# Sheet1.net
KiCad netlist of a schematic drawn in Altium Designer
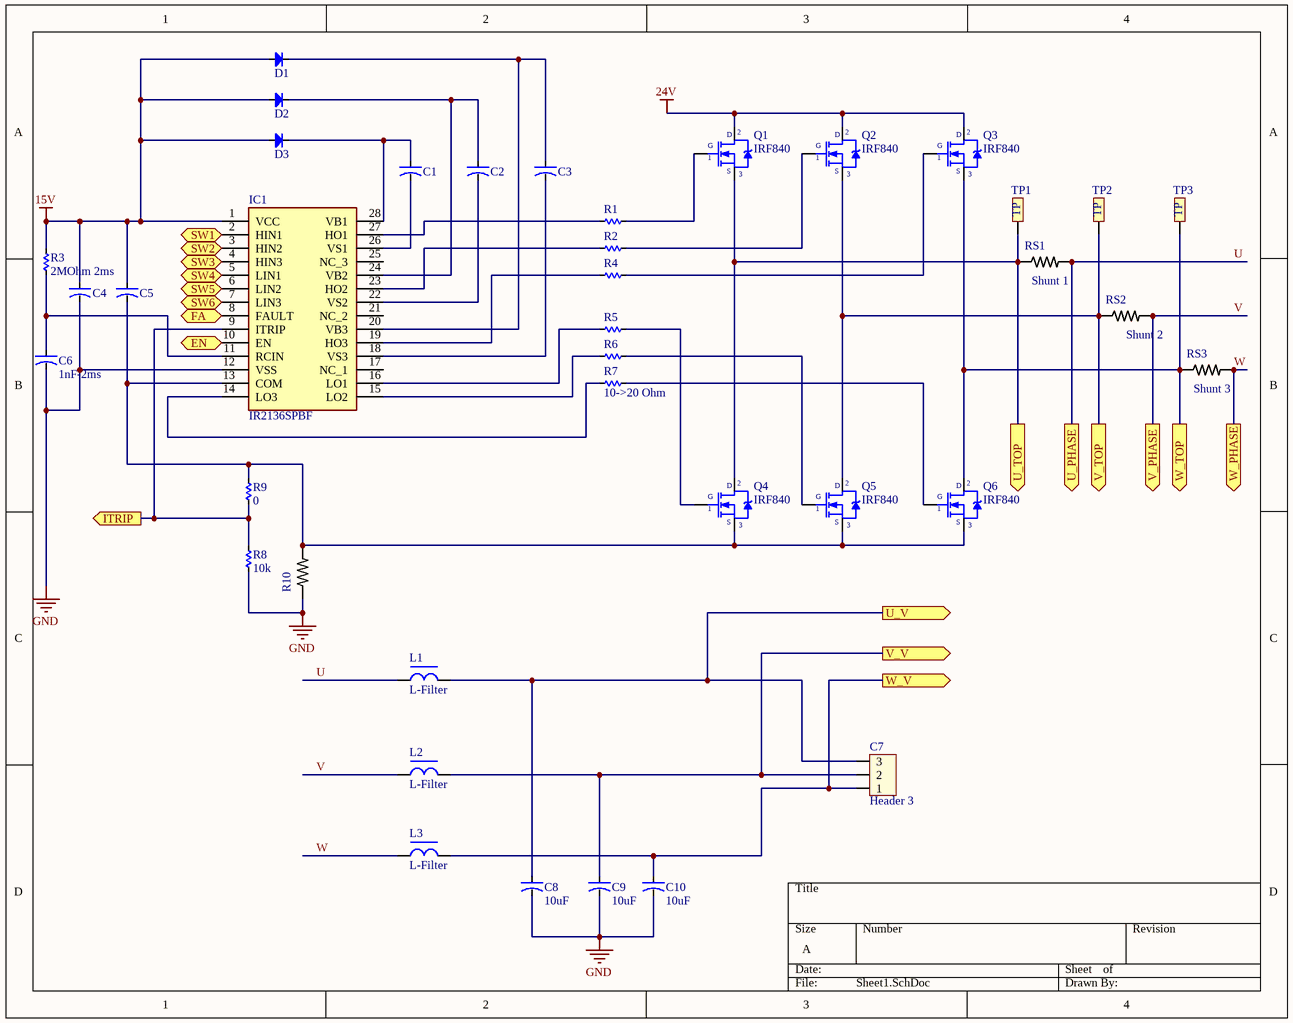
[diagram p0: Sheet1.SchDoc]

(export (version "E")
  (design (tool "Eeschema 10.0.6"))
  (components
    (comp (ref "C1")
      (value "50-100uF")
      (footprint "CA-ALU-5R")
      (description "Capacitor (Semiconductor SIM Model)")
      (fields (field (name "PUBLISHER") "Altium Limited"))
      (libsource (lib "LIBRARY") (part "CN-ALU-DIP"))
    )
    (comp (ref "C2")
      (value "50-100uF")
      (footprint "CA-ALU-5R")
      (description "Capacitor (Semiconductor SIM Model)")
      (fields (field (name "PUBLISHER") "Altium Limited"))
      (libsource (lib "LIBRARY") (part "CN-ALU-DIP"))
    )
    (comp (ref "C3")
      (value "50-100uF")
      (footprint "CA-ALU-5R")
      (description "Capacitor (Semiconductor SIM Model)")
      (fields (field (name "PUBLISHER") "Altium Limited"))
      (libsource (lib "LIBRARY") (part "CN-ALU-DIP"))
    )
    (comp (ref "C4")
      (value "to")
      (footprint "CA-ALU-5R")
      (description "Capacitor (Semiconductor SIM Model)")
      (fields (field (name "PUBLISHER") "Altium Limited"))
      (libsource (lib "LIBRARY") (part "CN-ALU-DIP"))
    )
    (comp (ref "C5")
      (value "to")
      (footprint "CA-ALU-5R")
      (description "Capacitor (Semiconductor SIM Model)")
      (fields (field (name "PUBLISHER") "Altium Limited"))
      (libsource (lib "LIBRARY") (part "CN-ALU-DIP"))
    )
    (comp (ref "C6")
      (value "1nF-2ms")
      (footprint "CA-ALU-2.54")
      (description "Capacitor (Semiconductor SIM Model)")
      (fields (field (name "PUBLISHER") "Altium Limited"))
      (libsource (lib "LIBRARY") (part "CN-ALU-DIP"))
    )
    (comp (ref "C7")
      (value "Header 3")
      (footprint "HED3")
      (description "Header 3 (Green)")
      (libsource (lib "syhaunguyen") (part "Hed3"))
    )
    (comp (ref "C8")
      (value "10uF")
      (footprint "CA-ALU-5R")
      (description "Capacitor (Semiconductor SIM Model)")
      (fields (field (name "PUBLISHER") "Altium Limited"))
      (libsource (lib "LIBRARY") (part "CN-ALU-DIP"))
    )
    (comp (ref "C9")
      (value "10uF")
      (footprint "CA-ALU-5R")
      (description "Capacitor (Semiconductor SIM Model)")
      (fields (field (name "PUBLISHER") "Altium Limited"))
      (libsource (lib "LIBRARY") (part "CN-ALU-DIP"))
    )
    (comp (ref "C10")
      (value "10uF")
      (footprint "CA-ALU-5R")
      (description "Capacitor (Semiconductor SIM Model)")
      (fields (field (name "PUBLISHER") "Altium Limited"))
      (libsource (lib "LIBRARY") (part "CN-ALU-DIP"))
    )
    (comp (ref "D1")
      (value "Diode")
      (footprint "DIO-1A")
      (description "Default Diode")
      (fields (field (name "PUBLISHER") "Altium Limited"))
      (libsource (lib "LIBRARY") (part "Diode"))
    )
    (comp (ref "D2")
      (value "Diode")
      (footprint "DIO-1A")
      (description "Default Diode")
      (fields (field (name "PUBLISHER") "Altium Limited"))
      (libsource (lib "LIBRARY") (part "Diode"))
    )
    (comp (ref "D3")
      (value "Diode")
      (footprint "DIO-1A")
      (description "Default Diode")
      (fields (field (name "PUBLISHER") "Altium Limited"))
      (libsource (lib "LIBRARY") (part "Diode"))
    )
    (comp (ref "IC1")
      (value "IR2136SPBF")
      (footprint "SOIC127P1032X265-28N")
      (description "Integrated Circuit")
      (fields (field (name "MOUSER PART NUMBER") "942-IR2136SPBF") (field (name "RS PART NUMBER") "5412284P"))
      (libsource (lib "SemacSYS") (part "IR2136SPBF"))
    )
    (comp (ref "L1")
      (value "L-Filter")
      (footprint "L-DIP-M-5.3")
      (description "Inductor")
      (libsource (lib "LIBRARY") (part "L-DIP-1"))
    )
    (comp (ref "L2")
      (value "L-Filter")
      (footprint "L-DIP-M-5.3")
      (description "Inductor")
      (libsource (lib "LIBRARY") (part "L-DIP-1"))
    )
    (comp (ref "L3")
      (value "L-Filter")
      (footprint "L-DIP-M-5.3")
      (description "Inductor")
      (libsource (lib "LIBRARY") (part "L-DIP-1"))
    )
    (comp (ref "Q1")
      (value "IRF840")
      (footprint "TO220-123")
      (description "MOSFET N - CHANNEL 500V - 0.75 - 8A - TO-220")
      (libsource (lib "LIBRARY") (part "IRF840"))
    )
    (comp (ref "Q2")
      (value "IRF840")
      (footprint "TO220-123")
      (description "MOSFET N - CHANNEL 500V - 0.75 - 8A - TO-220")
      (libsource (lib "LIBRARY") (part "IRF840"))
    )
    (comp (ref "Q3")
      (value "IRF840")
      (footprint "TO220-123")
      (description "MOSFET N - CHANNEL 500V - 0.75 - 8A - TO-220")
      (libsource (lib "LIBRARY") (part "IRF840"))
    )
    (comp (ref "Q4")
      (value "IRF840")
      (footprint "TO220-123")
      (description "MOSFET N - CHANNEL 500V - 0.75 - 8A - TO-220")
      (libsource (lib "LIBRARY") (part "IRF840"))
    )
    (comp (ref "Q5")
      (value "IRF840")
      (footprint "TO220-123")
      (description "MOSFET N - CHANNEL 500V - 0.75 - 8A - TO-220")
      (libsource (lib "LIBRARY") (part "IRF840"))
    )
    (comp (ref "Q6")
      (value "IRF840")
      (footprint "TO220-123")
      (description "MOSFET N - CHANNEL 500V - 0.75 - 8A - TO-220")
      (libsource (lib "LIBRARY") (part "IRF840"))
    )
    (comp (ref "R1")
      (value "10->20 Ohm")
      (footprint "RES-1/2W")
      (description "Res")
      (fields
        (field (name "MANUFACTURER") "Generic Components")
        (field (name "PUBLISHER") "Altium Hobart Technology Centre")
      )
      (libsource (lib "LIBRARY1") (part "Res"))
    )
    (comp (ref "R2")
      (value "1K10->20 Ohm")
      (footprint "RES-1/2W")
      (description "Res")
      (fields
        (field (name "MANUFACTURER") "Generic Components")
        (field (name "PUBLISHER") "Altium Hobart Technology Centre")
      )
      (libsource (lib "LIBRARY1") (part "Res"))
    )
    (comp (ref "R3")
      (value "2MOhm 2ms")
      (footprint "RES-1/2W")
      (description "Res")
      (fields
        (field (name "MANUFACTURER") "Generic Components")
        (field (name "PUBLISHER") "Altium Hobart Technology Centre")
      )
      (libsource (lib "LIBRARY1") (part "Res"))
    )
    (comp (ref "R4")
      (value "10->20 Ohm")
      (footprint "RES-1/2W")
      (description "Res")
      (fields
        (field (name "MANUFACTURER") "Generic Components")
        (field (name "PUBLISHER") "Altium Hobart Technology Centre")
      )
      (libsource (lib "LIBRARY1") (part "Res"))
    )
    (comp (ref "R5")
      (value "10->20 Ohm")
      (footprint "RES-1/2W")
      (description "Res")
      (fields
        (field (name "MANUFACTURER") "Generic Components")
        (field (name "PUBLISHER") "Altium Hobart Technology Centre")
      )
      (libsource (lib "LIBRARY1") (part "Res"))
    )
    (comp (ref "R6")
      (value "10->20 Ohm")
      (footprint "RES-1/2W")
      (description "Res")
      (fields
        (field (name "MANUFACTURER") "Generic Components")
        (field (name "PUBLISHER") "Altium Hobart Technology Centre")
      )
      (libsource (lib "LIBRARY1") (part "Res"))
    )
    (comp (ref "R7")
      (value "10->20 Ohm")
      (footprint "RES-1/2W")
      (description "Res")
      (fields
        (field (name "MANUFACTURER") "Generic Components")
        (field (name "PUBLISHER") "Altium Hobart Technology Centre")
      )
      (libsource (lib "LIBRARY1") (part "Res"))
    )
    (comp (ref "R8")
      (value "10k")
      (footprint "RES-1/2W")
      (description "Res")
      (fields
        (field (name "MANUFACTURER") "Generic Components")
        (field (name "PUBLISHER") "Altium Hobart Technology Centre")
      )
      (libsource (lib "LIBRARY1") (part "Res"))
    )
    (comp (ref "R9")
      (value "0")
      (footprint "RES-1/2W")
      (description "Res")
      (fields
        (field (name "MANUFACTURER") "Generic Components")
        (field (name "PUBLISHER") "Altium Hobart Technology Centre")
      )
      (libsource (lib "LIBRARY1") (part "Res"))
    )
    (comp (ref "R10")
      (value "1-1625873-0")
      (footprint "*RESAD640W45L370D200")
      (description "RS LR0204 RESISTOR KIT")
      (fields (field (name "MF") "TE Connectivity AMP Connectors") (field (name "MP") "RES KIT LR0204R"))
      (libsource (lib "RES_KIT_LR0204R") (part "RES_KIT_LR0204R"))
    )
    (comp (ref "RS1")
      (value "1-1625873-0")
      (footprint "*RESAD640W45L370D200")
      (description "RS LR0204 RESISTOR KIT")
      (fields (field (name "MF") "TE Connectivity AMP Connectors") (field (name "MP") "RES KIT LR0204R"))
      (libsource (lib "SemacSYS") (part "RES_KIT_LR0204R"))
    )
    (comp (ref "RS2")
      (value "1-1625873-0")
      (footprint "*RESAD640W45L370D200")
      (description "RS LR0204 RESISTOR KIT")
      (fields (field (name "MF") "TE Connectivity AMP Connectors") (field (name "MP") "RES KIT LR0204R"))
      (libsource (lib "SemacSYS") (part "RES_KIT_LR0204R"))
    )
    (comp (ref "RS3")
      (value "1-1625873-0")
      (footprint "*RESAD640W45L370D200")
      (description "RS LR0204 RESISTOR KIT")
      (fields (field (name "MF") "TE Connectivity AMP Connectors") (field (name "MP") "RES KIT LR0204R"))
      (libsource (lib "SemacSYS") (part "RES_KIT_LR0204R"))
    )
    (comp (ref "TP1")
      (value "~")
      (footprint "TP")
      (description "CONNECT 1")
      (libsource (lib "syhaunguyen") (part "TP"))
    )
    (comp (ref "TP2")
      (value "~")
      (footprint "TP")
      (description "CONNECT 1")
      (libsource (lib "syhaunguyen") (part "TP"))
    )
    (comp (ref "TP3")
      (value "~")
      (footprint "TP")
      (description "CONNECT 1")
      (libsource (lib "syhaunguyen") (part "TP"))
    )
  )
  (nets
    (net (code "1") (name "/EN") (class "Default")
      (node (ref "IC1") (pin "10") (pinfunction "EN_10") (pintype "passive"))
    )
    (net (code "2") (name "/FA") (class "Default")
      (node (ref "IC1") (pin "8") (pinfunction "FAULT_8") (pintype "passive"))
    )
    (net (code "3") (name "/ITRIP") (class "Default")
      (node (ref "IC1") (pin "9") (pinfunction "ITRIP_9") (pintype "passive"))
      (node (ref "R8") (pin "1") (pinfunction "1_1") (pintype "passive"))
      (node (ref "R9") (pin "2") (pinfunction "2_2") (pintype "passive"))
    )
    (net (code "4") (name "/SW1") (class "Default")
      (node (ref "IC1") (pin "2") (pinfunction "HIN1_2") (pintype "passive"))
    )
    (net (code "5") (name "/SW2") (class "Default")
      (node (ref "IC1") (pin "3") (pinfunction "HIN2_3") (pintype "passive"))
    )
    (net (code "6") (name "/SW3") (class "Default")
      (node (ref "IC1") (pin "4") (pinfunction "HIN3_4") (pintype "passive"))
    )
    (net (code "7") (name "/SW4") (class "Default")
      (node (ref "IC1") (pin "5") (pinfunction "LIN1_5") (pintype "passive"))
    )
    (net (code "8") (name "/SW5") (class "Default")
      (node (ref "IC1") (pin "6") (pinfunction "LIN2_6") (pintype "passive"))
    )
    (net (code "9") (name "/SW6") (class "Default")
      (node (ref "IC1") (pin "7") (pinfunction "LIN3_7") (pintype "passive"))
    )
    (net (code "10") (name "/U") (class "Default")
      (node (ref "L1") (pin "1") (pinfunction "1_1") (pintype "passive"))
      (node (ref "RS1") (pin "2") (pinfunction "2_2") (pintype "passive"))
    )
    (net (code "11") (name "/U_TOP") (class "Default")
      (node (ref "Q1") (pin "3") (pinfunction "S_3") (pintype "passive"))
      (node (ref "Q4") (pin "2") (pinfunction "D_2") (pintype "passive"))
      (node (ref "RS1") (pin "1") (pinfunction "1_1") (pintype "passive"))
      (node (ref "TP1") (pin "TP1") (pinfunction "0_TP1") (pintype "passive"))
    )
    (net (code "12") (name "/U_V") (class "Default")
      (node (ref "C7") (pin "3") (pinfunction "3_3") (pintype "passive"))
      (node (ref "C8") (pin "1") (pinfunction "1_1") (pintype "passive"))
      (node (ref "L1") (pin "2") (pinfunction "2_2") (pintype "passive"))
    )
    (net (code "13") (name "/V") (class "Default")
      (node (ref "L2") (pin "1") (pinfunction "1_1") (pintype "passive"))
      (node (ref "RS2") (pin "2") (pinfunction "2_2") (pintype "passive"))
    )
    (net (code "14") (name "/V_TOP") (class "Default")
      (node (ref "Q2") (pin "3") (pinfunction "S_3") (pintype "passive"))
      (node (ref "Q5") (pin "2") (pinfunction "D_2") (pintype "passive"))
      (node (ref "RS2") (pin "1") (pinfunction "1_1") (pintype "passive"))
      (node (ref "TP2") (pin "TP1") (pinfunction "0_TP1") (pintype "passive"))
    )
    (net (code "15") (name "/V_V") (class "Default")
      (node (ref "C7") (pin "2") (pinfunction "2_2") (pintype "passive"))
      (node (ref "C9") (pin "1") (pinfunction "1_1") (pintype "passive"))
      (node (ref "L2") (pin "2") (pinfunction "2_2") (pintype "passive"))
    )
    (net (code "16") (name "/W") (class "Default")
      (node (ref "L3") (pin "1") (pinfunction "1_1") (pintype "passive"))
      (node (ref "RS3") (pin "2") (pinfunction "2_2") (pintype "passive"))
    )
    (net (code "17") (name "/W_TOP") (class "Default")
      (node (ref "Q3") (pin "3") (pinfunction "S_3") (pintype "passive"))
      (node (ref "Q6") (pin "2") (pinfunction "D_2") (pintype "passive"))
      (node (ref "RS3") (pin "1") (pinfunction "1_1") (pintype "passive"))
      (node (ref "TP3") (pin "TP1") (pinfunction "0_TP1") (pintype "passive"))
    )
    (net (code "18") (name "/W_V") (class "Default")
      (node (ref "C10") (pin "1") (pinfunction "1_1") (pintype "passive"))
      (node (ref "C7") (pin "1") (pinfunction "1_1") (pintype "passive"))
      (node (ref "L3") (pin "2") (pinfunction "2_2") (pintype "passive"))
    )
    (net (code "19") (name "15V") (class "Default")
      (node (ref "C4") (pin "1") (pinfunction "1_1") (pintype "passive"))
      (node (ref "C5") (pin "1") (pinfunction "1_1") (pintype "passive"))
      (node (ref "D1") (pin "1") (pinfunction "A_1") (pintype "passive"))
      (node (ref "D2") (pin "1") (pinfunction "A_1") (pintype "passive"))
      (node (ref "D3") (pin "1") (pinfunction "A_1") (pintype "passive"))
      (node (ref "IC1") (pin "1") (pinfunction "VCC_1") (pintype "passive"))
      (node (ref "R3") (pin "1") (pinfunction "1_1") (pintype "passive"))
    )
    (net (code "20") (name "24V") (class "Default")
      (node (ref "Q1") (pin "2") (pinfunction "D_2") (pintype "passive"))
      (node (ref "Q2") (pin "2") (pinfunction "D_2") (pintype "passive"))
      (node (ref "Q3") (pin "2") (pinfunction "D_2") (pintype "passive"))
    )
    (net (code "21") (name "GND") (class "Default")
      (node (ref "C10") (pin "2") (pinfunction "2_2") (pintype "passive"))
      (node (ref "C4") (pin "2") (pinfunction "2_2") (pintype "passive"))
      (node (ref "C6") (pin "2") (pinfunction "2_2") (pintype "passive"))
      (node (ref "C8") (pin "2") (pinfunction "2_2") (pintype "passive"))
      (node (ref "C9") (pin "2") (pinfunction "2_2") (pintype "passive"))
      (node (ref "IC1") (pin "12") (pinfunction "VSS_12") (pintype "passive"))
      (node (ref "R10") (pin "1") (pinfunction "1_1") (pintype "passive"))
      (node (ref "R8") (pin "2") (pinfunction "2_2") (pintype "passive"))
    )
    (net (code "22") (name "Net-(D1-K)") (class "Default")
      (node (ref "C3") (pin "1") (pinfunction "1_1") (pintype "passive"))
      (node (ref "D1") (pin "2") (pinfunction "K_2") (pintype "passive"))
      (node (ref "IC1") (pin "20") (pinfunction "VB3_20") (pintype "passive"))
    )
    (net (code "23") (name "Net-(D2-K)") (class "Default")
      (node (ref "C2") (pin "1") (pinfunction "1_1") (pintype "passive"))
      (node (ref "D2") (pin "2") (pinfunction "K_2") (pintype "passive"))
      (node (ref "IC1") (pin "24") (pinfunction "VB2_24") (pintype "passive"))
    )
    (net (code "24") (name "Net-(D3-K)") (class "Default")
      (node (ref "C1") (pin "1") (pinfunction "1_1") (pintype "passive"))
      (node (ref "D3") (pin "2") (pinfunction "K_2") (pintype "passive"))
      (node (ref "IC1") (pin "28") (pinfunction "VB1_28") (pintype "passive"))
    )
    (net (code "25") (name "Net-(IC1-COM)") (class "Default")
      (node (ref "C5") (pin "2") (pinfunction "2_2") (pintype "passive"))
      (node (ref "IC1") (pin "13") (pinfunction "COM_13") (pintype "passive"))
      (node (ref "Q4") (pin "3") (pinfunction "S_3") (pintype "passive"))
      (node (ref "Q5") (pin "3") (pinfunction "S_3") (pintype "passive"))
      (node (ref "Q6") (pin "3") (pinfunction "S_3") (pintype "passive"))
      (node (ref "R10") (pin "2") (pinfunction "2_2") (pintype "passive"))
      (node (ref "R9") (pin "1") (pinfunction "1_1") (pintype "passive"))
    )
    (net (code "26") (name "Net-(IC1-HO1)") (class "Default")
      (node (ref "IC1") (pin "27") (pinfunction "HO1_27") (pintype "passive"))
      (node (ref "R1") (pin "2") (pinfunction "2_2") (pintype "passive"))
    )
    (net (code "27") (name "Net-(IC1-HO2)") (class "Default")
      (node (ref "IC1") (pin "23") (pinfunction "HO2_23") (pintype "passive"))
      (node (ref "R2") (pin "2") (pinfunction "2_2") (pintype "passive"))
    )
    (net (code "28") (name "Net-(IC1-HO3)") (class "Default")
      (node (ref "IC1") (pin "19") (pinfunction "HO3_19") (pintype "passive"))
      (node (ref "R4") (pin "2") (pinfunction "2_2") (pintype "passive"))
    )
    (net (code "29") (name "Net-(IC1-LO1)") (class "Default")
      (node (ref "IC1") (pin "16") (pinfunction "LO1_16") (pintype "passive"))
      (node (ref "R5") (pin "2") (pinfunction "2_2") (pintype "passive"))
    )
    (net (code "30") (name "Net-(IC1-LO2)") (class "Default")
      (node (ref "IC1") (pin "15") (pinfunction "LO2_15") (pintype "passive"))
      (node (ref "R6") (pin "2") (pinfunction "2_2") (pintype "passive"))
    )
    (net (code "31") (name "Net-(IC1-LO3)") (class "Default")
      (node (ref "IC1") (pin "14") (pinfunction "LO3_14") (pintype "passive"))
      (node (ref "R7") (pin "2") (pinfunction "2_2") (pintype "passive"))
    )
    (net (code "32") (name "Net-(IC1-RCIN)") (class "Default")
      (node (ref "C6") (pin "1") (pinfunction "1_1") (pintype "passive"))
      (node (ref "IC1") (pin "11") (pinfunction "RCIN_11") (pintype "passive"))
      (node (ref "R3") (pin "2") (pinfunction "2_2") (pintype "passive"))
    )
    (net (code "33") (name "Net-(IC1-VS1)") (class "Default")
      (node (ref "C1") (pin "2") (pinfunction "2_2") (pintype "passive"))
      (node (ref "IC1") (pin "26") (pinfunction "VS1_26") (pintype "passive"))
    )
    (net (code "34") (name "Net-(IC1-VS2)") (class "Default")
      (node (ref "C2") (pin "2") (pinfunction "2_2") (pintype "passive"))
      (node (ref "IC1") (pin "22") (pinfunction "VS2_22") (pintype "passive"))
    )
    (net (code "35") (name "Net-(IC1-VS3)") (class "Default")
      (node (ref "C3") (pin "2") (pinfunction "2_2") (pintype "passive"))
      (node (ref "IC1") (pin "18") (pinfunction "VS3_18") (pintype "passive"))
    )
    (net (code "36") (name "Net-(Q1-G)") (class "Default")
      (node (ref "Q1") (pin "1") (pinfunction "G_1") (pintype "passive"))
      (node (ref "R1") (pin "1") (pinfunction "1_1") (pintype "passive"))
    )
    (net (code "37") (name "Net-(Q2-G)") (class "Default")
      (node (ref "Q2") (pin "1") (pinfunction "G_1") (pintype "passive"))
      (node (ref "R2") (pin "1") (pinfunction "1_1") (pintype "passive"))
    )
    (net (code "38") (name "Net-(Q3-G)") (class "Default")
      (node (ref "Q3") (pin "1") (pinfunction "G_1") (pintype "passive"))
      (node (ref "R4") (pin "1") (pinfunction "1_1") (pintype "passive"))
    )
    (net (code "39") (name "Net-(Q4-G)") (class "Default")
      (node (ref "Q4") (pin "1") (pinfunction "G_1") (pintype "passive"))
      (node (ref "R5") (pin "1") (pinfunction "1_1") (pintype "passive"))
    )
    (net (code "40") (name "Net-(Q5-G)") (class "Default")
      (node (ref "Q5") (pin "1") (pinfunction "G_1") (pintype "passive"))
      (node (ref "R6") (pin "1") (pinfunction "1_1") (pintype "passive"))
    )
    (net (code "41") (name "Net-(Q6-G)") (class "Default")
      (node (ref "Q6") (pin "1") (pinfunction "G_1") (pintype "passive"))
      (node (ref "R7") (pin "1") (pinfunction "1_1") (pintype "passive"))
    )
    (net (code "42") (name "unconnected-(IC1-NC_1-Pad17)") (class "Default")
      (node (ref "IC1") (pin "17") (pinfunction "NC_1_17") (pintype "passive"))
    )
    (net (code "43") (name "unconnected-(IC1-NC_2-Pad21)") (class "Default")
      (node (ref "IC1") (pin "21") (pinfunction "NC_2_21") (pintype "passive"))
    )
    (net (code "44") (name "unconnected-(IC1-NC_3-Pad25)") (class "Default")
      (node (ref "IC1") (pin "25") (pinfunction "NC_3_25") (pintype "passive"))
    )
  )
)
